# board_revA.net
KiCad netlist of a schematic drawn in EAGLE
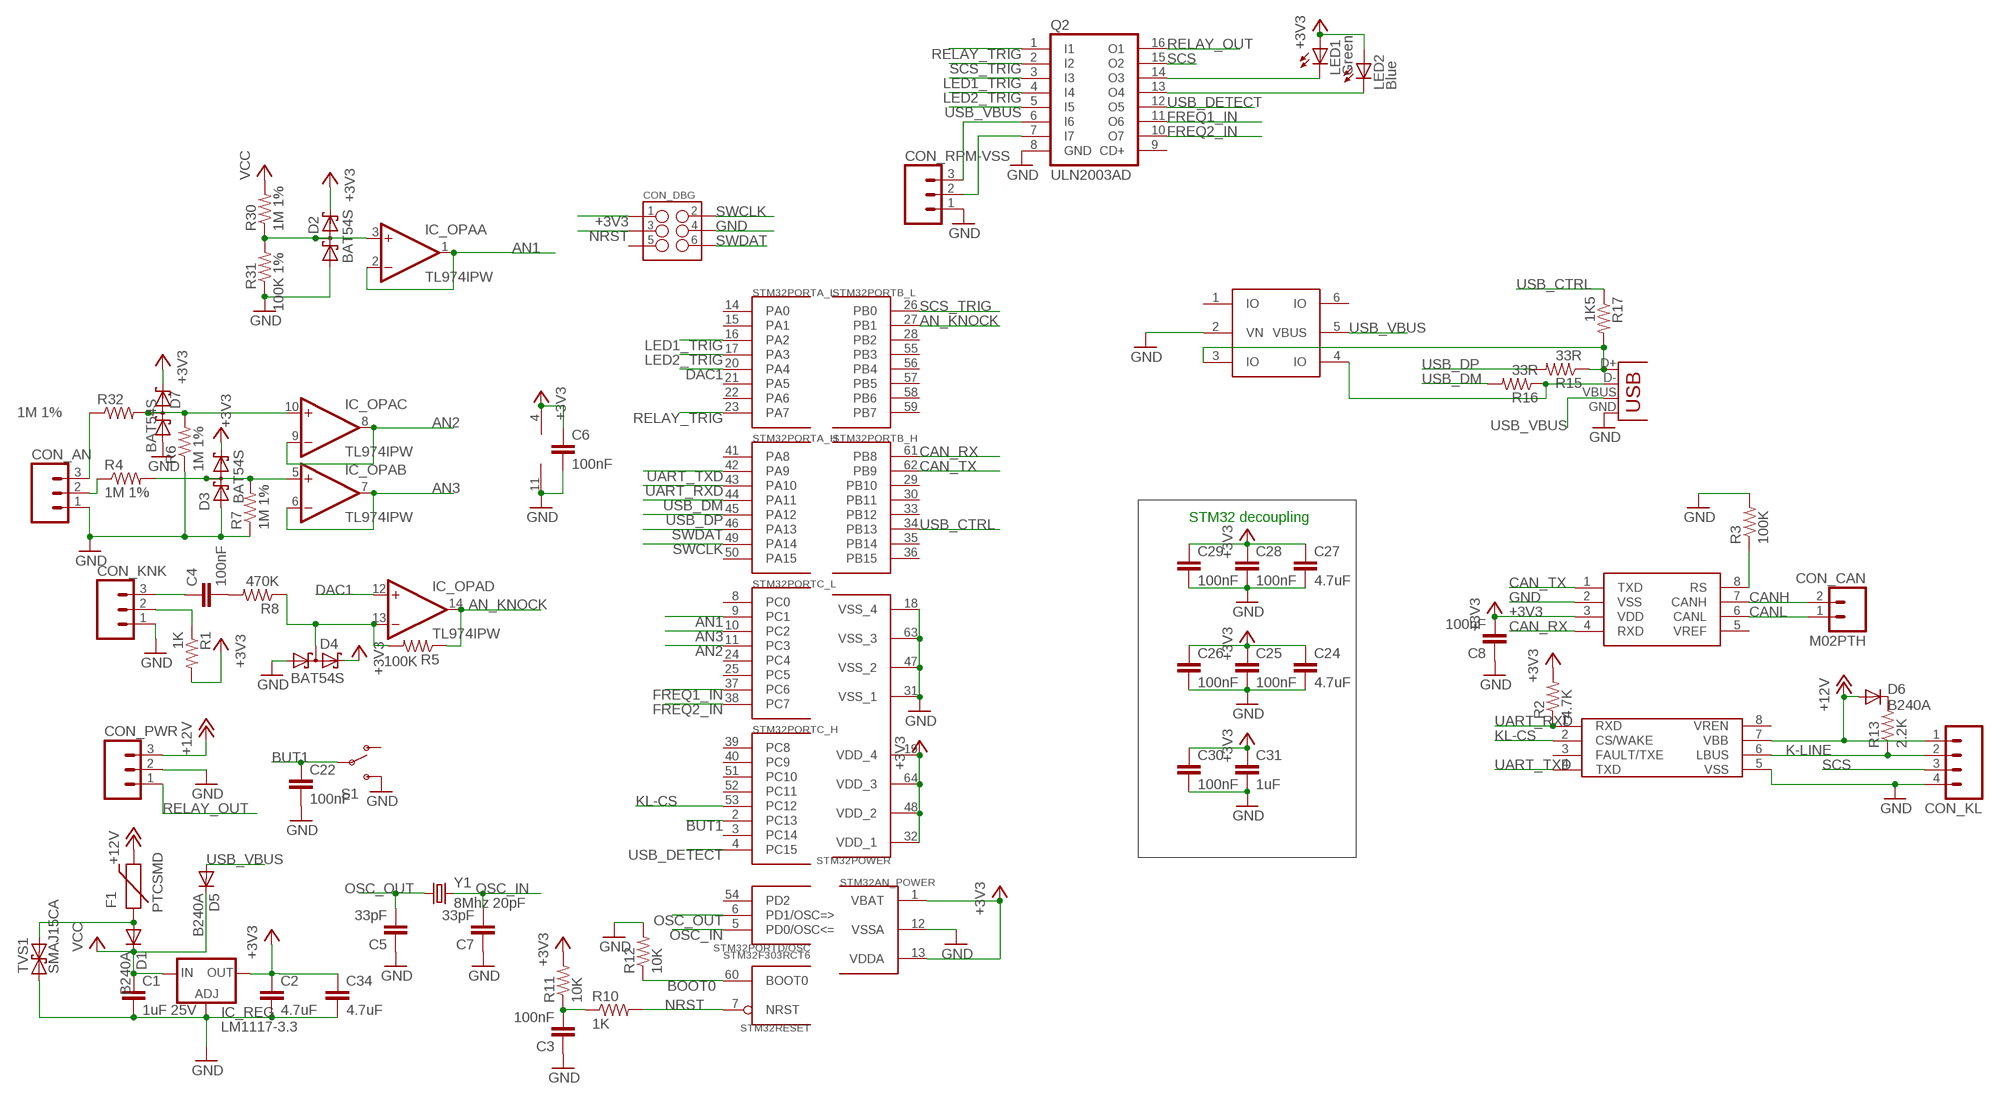
[diagram p0: schematic, sheet 1]

(export (version "E")
  (design (tool "Eeschema 10.0.6"))
  (components
    (comp (ref "C1")
      (value "1uF 25V")
      (footprint "eagle-import:0603-CAP")
      (libsource (lib "eagle-import") (part "SparkFun-Passives_CAP0603-CAP"))
    )
    (comp (ref "C2")
      (value "4.7uF")
      (footprint "eagle-import:0603-CAP")
      (libsource (lib "eagle-import") (part "SparkFun-Passives_CAP0603-CAP"))
    )
    (comp (ref "C3")
      (value "100nF")
      (footprint "eagle-import:0603-CAP")
      (libsource (lib "eagle-import") (part "CAP0603-CAP"))
    )
    (comp (ref "C4")
      (value "100nF")
      (footprint "eagle-import:0603-CAP")
      (libsource (lib "eagle-import") (part "CAP0603-CAP"))
    )
    (comp (ref "C5")
      (value "33pF")
      (footprint "eagle-import:0603-CAP")
      (libsource (lib "eagle-import") (part "CAP0603-CAP"))
    )
    (comp (ref "C6")
      (value "100nF")
      (footprint "eagle-import:0603-CAP")
      (libsource (lib "eagle-import") (part "CAP0603-CAP"))
    )
    (comp (ref "C7")
      (value "33pF")
      (footprint "eagle-import:0603-CAP")
      (libsource (lib "eagle-import") (part "CAP0603-CAP"))
    )
    (comp (ref "C8")
      (value "100nF")
      (footprint "eagle-import:0603-CAP")
      (libsource (lib "eagle-import") (part "CAP0603-CAP"))
    )
    (comp (ref "C22")
      (value "100nF")
      (footprint "eagle-import:0603-CAP")
      (libsource (lib "eagle-import") (part "CAP0603-CAP"))
    )
    (comp (ref "C24")
      (value "4.7uF")
      (footprint "eagle-import:0603-CAP")
      (libsource (lib "eagle-import") (part "SparkFun-Passives_CAP0603-CAP"))
    )
    (comp (ref "C25")
      (value "100nF")
      (footprint "eagle-import:0603-CAP")
      (libsource (lib "eagle-import") (part "CAP0603-CAP"))
    )
    (comp (ref "C26")
      (value "100nF")
      (footprint "eagle-import:0603-CAP")
      (libsource (lib "eagle-import") (part "CAP0603-CAP"))
    )
    (comp (ref "C27")
      (value "4.7uF")
      (footprint "eagle-import:0603-CAP")
      (libsource (lib "eagle-import") (part "SparkFun-Passives_CAP0603-CAP"))
    )
    (comp (ref "C28")
      (value "100nF")
      (footprint "eagle-import:0603-CAP")
      (libsource (lib "eagle-import") (part "CAP0603-CAP"))
    )
    (comp (ref "C29")
      (value "100nF")
      (footprint "eagle-import:0603-CAP")
      (libsource (lib "eagle-import") (part "CAP0603-CAP"))
    )
    (comp (ref "C30")
      (value "100nF")
      (footprint "eagle-import:0603-CAP")
      (libsource (lib "eagle-import") (part "CAP0603-CAP"))
    )
    (comp (ref "C31")
      (value "1uF")
      (footprint "eagle-import:0603-CAP")
      (libsource (lib "eagle-import") (part "CAP0603-CAP"))
    )
    (comp (ref "C34")
      (value "4.7uF")
      (footprint "eagle-import:0603-CAP")
      (libsource (lib "eagle-import") (part "SparkFun-Passives_CAP0603-CAP"))
    )
    (comp (ref "CON_AN")
      (value "M03PTH")
      (footprint "eagle-import:1X03")
      (libsource (lib "eagle-import") (part "M03PTH"))
    )
    (comp (ref "CON_CAN")
      (value "M02PTH")
      (footprint "eagle-import:1X02")
      (libsource (lib "eagle-import") (part "M02PTH"))
    )
    (comp (ref "CON_DBG")
      (value "M03X22X3_SILK_SM")
      (footprint "eagle-import:2X3")
      (libsource (lib "eagle-import") (part "M03X22X3_SILK_SM"))
    )
    (comp (ref "CON_KL")
      (value "M04PTH")
      (footprint "eagle-import:1X04")
      (libsource (lib "eagle-import") (part "M04PTH"))
    )
    (comp (ref "CON_KNK")
      (value "M03PTH")
      (footprint "eagle-import:1X03")
      (libsource (lib "eagle-import") (part "M03PTH"))
    )
    (comp (ref "CON_PWR")
      (value "M03PTH")
      (footprint "eagle-import:1X03")
      (libsource (lib "eagle-import") (part "M03PTH"))
    )
    (comp (ref "CON_RPM-VSS")
      (value "M03PTH")
      (footprint "eagle-import:1X03")
      (libsource (lib "eagle-import") (part "M03PTH"))
    )
    (comp (ref "CON_USB")
      (value "USBSMD")
      (footprint "eagle-import:USB-MINIB")
      (libsource (lib "eagle-import") (part "USBSMD"))
    )
    (comp (ref "D1")
      (value "B240A")
      (footprint "eagle-import:SMA-DIODE")
      (libsource (lib "eagle-import") (part "DIODESMA"))
    )
    (comp (ref "D2")
      (value "BAT54S")
      (footprint "eagle-import:SOT23")
      (libsource (lib "eagle-import") (part "BAT54S"))
    )
    (comp (ref "D3")
      (value "BAT54S")
      (footprint "eagle-import:SOT23")
      (libsource (lib "eagle-import") (part "BAT54S"))
    )
    (comp (ref "D4")
      (value "BAT54S")
      (footprint "eagle-import:SOT23")
      (libsource (lib "eagle-import") (part "BAT54S"))
    )
    (comp (ref "D5")
      (value "B240A")
      (footprint "eagle-import:SMA-DIODE")
      (libsource (lib "eagle-import") (part "DIODESMA"))
    )
    (comp (ref "D6")
      (value "B240A")
      (footprint "eagle-import:SMA-DIODE")
      (libsource (lib "eagle-import") (part "DIODESMA"))
    )
    (comp (ref "D7")
      (value "BAT54S")
      (footprint "eagle-import:SOT23")
      (libsource (lib "eagle-import") (part "BAT54S"))
    )
    (comp (ref "F1")
      (value "PTCSMD")
      (footprint "eagle-import:PTC-1206")
      (libsource (lib "eagle-import") (part "PTCSMD"))
    )
    (comp (ref "IC_CAN")
      (value "MAX3051")
      (footprint "eagle-import:SO08")
      (libsource (lib "eagle-import") (part "MCP2551"))
    )
    (comp (ref "IC_KLINE")
      (value "MCP2004")
      (footprint "eagle-import:SO08")
      (libsource (lib "eagle-import") (part "MCP2004"))
    )
    (comp (ref "IC_OPA")
      (value "TL974IPW")
      (footprint "eagle-import:TSSOP14")
      (libsource (lib "eagle-import") (part "LMV324?MZ"))
    )
    (comp (ref "IC_REG")
      (value "LM1117-3.3")
      (footprint "eagle-import:DPACK")
      (libsource (lib "eagle-import") (part "LD117A?DT33TR"))
    )
    (comp (ref "LED1")
      (value "Green")
      (footprint "eagle-import:LED3MM")
      (libsource (lib "eagle-import") (part "LED3MM"))
    )
    (comp (ref "LED2")
      (value "Blue")
      (footprint "eagle-import:LED3MM")
      (libsource (lib "eagle-import") (part "LED3MM"))
    )
    (comp (ref "Q2")
      (value "ULN2003AD")
      (footprint "eagle-import:SO16")
      (libsource (lib "eagle-import") (part "ULN2003AD"))
    )
    (comp (ref "R1")
      (value "1K")
      (footprint "eagle-import:0603-RES")
      (libsource (lib "eagle-import") (part "RESISTOR0603-RES"))
    )
    (comp (ref "R2")
      (value "4.7K")
      (footprint "eagle-import:0603-RES")
      (libsource (lib "eagle-import") (part "RESISTOR0603-RES"))
    )
    (comp (ref "R3")
      (value "100K")
      (footprint "eagle-import:0603-RES")
      (libsource (lib "eagle-import") (part "RESISTOR0603-RES"))
    )
    (comp (ref "R4")
      (value "1M 1%")
      (footprint "eagle-import:0603-RES")
      (libsource (lib "eagle-import") (part "RESISTOR0603-RES"))
    )
    (comp (ref "R5")
      (value "100K")
      (footprint "eagle-import:0603-RES")
      (libsource (lib "eagle-import") (part "RESISTOR0603-RES"))
    )
    (comp (ref "R6")
      (value "1M 1%")
      (footprint "eagle-import:0603-RES")
      (libsource (lib "eagle-import") (part "RESISTOR0603-RES"))
    )
    (comp (ref "R7")
      (value "1M 1%")
      (footprint "eagle-import:0603-RES")
      (libsource (lib "eagle-import") (part "RESISTOR0603-RES"))
    )
    (comp (ref "R8")
      (value "470K")
      (footprint "eagle-import:0603-RES")
      (libsource (lib "eagle-import") (part "RESISTOR0603-RES"))
    )
    (comp (ref "R10")
      (value "1K")
      (footprint "eagle-import:0603-RES")
      (libsource (lib "eagle-import") (part "RESISTOR0603-RES"))
    )
    (comp (ref "R11")
      (value "10K")
      (footprint "eagle-import:0603-RES")
      (libsource (lib "eagle-import") (part "RESISTOR0603-RES"))
    )
    (comp (ref "R12")
      (value "10K")
      (footprint "eagle-import:0603-RES")
      (libsource (lib "eagle-import") (part "RESISTOR0603-RES"))
    )
    (comp (ref "R13")
      (value "2.2K")
      (footprint "eagle-import:0603-RES")
      (libsource (lib "eagle-import") (part "RESISTOR0603-RES"))
    )
    (comp (ref "R15")
      (value "33R")
      (footprint "eagle-import:0603-RES")
      (libsource (lib "eagle-import") (part "RESISTOR0603-RES"))
    )
    (comp (ref "R16")
      (value "33R")
      (footprint "eagle-import:0603-RES")
      (libsource (lib "eagle-import") (part "RESISTOR0603-RES"))
    )
    (comp (ref "R17")
      (value "1K5")
      (footprint "eagle-import:0603-RES")
      (libsource (lib "eagle-import") (part "RESISTOR0603-RES"))
    )
    (comp (ref "R30")
      (value "1M 1%")
      (footprint "eagle-import:0603-RES")
      (libsource (lib "eagle-import") (part "RESISTOR0603-RES"))
    )
    (comp (ref "R31")
      (value "100K 1%")
      (footprint "eagle-import:0603-RES")
      (libsource (lib "eagle-import") (part "RESISTOR0603-RES"))
    )
    (comp (ref "R32")
      (value "1M 1%")
      (footprint "eagle-import:0603-RES")
      (libsource (lib "eagle-import") (part "RESISTOR0603-RES"))
    )
    (comp (ref "S1")
      (value "SWITCH-SPDTPTH")
      (footprint "eagle-import:SWITCH-SPDT")
      (libsource (lib "eagle-import") (part "SWITCH-SPDTPTH"))
    )
    (comp (ref "STM32")
      (value "STM32F303RCT6")
      (footprint "eagle-import:TQFP64")
      (libsource (lib "eagle-import") (part "STM32F10XRXT6"))
    )
    (comp (ref "TVS1")
      (value "SMAJ15CA")
      (footprint "eagle-import:SMA-DIODE")
      (libsource (lib "eagle-import") (part "TVS"))
    )
    (comp (ref "TVS2")
      (value "NUP4201MR6")
      (footprint "eagle-import:SOT23-6")
      (libsource (lib "eagle-import") (part "NUP4201MR6"))
    )
    (comp (ref "Y1")
      (value "8Mhz 20pF")
      (footprint "eagle-import:HC49US")
      (libsource (lib "eagle-import") (part "CRYSTALHC49US"))
    )
  )
  (nets
    (net (code "1") (name "+3V3") (class "Default")
      (node (ref "C2") (pin "1") (pinfunction "1_1") (pintype "passive"))
      (node (ref "C24") (pin "1") (pinfunction "1_1") (pintype "passive"))
      (node (ref "C25") (pin "1") (pinfunction "1_1") (pintype "passive"))
      (node (ref "C26") (pin "1") (pinfunction "1_1") (pintype "passive"))
      (node (ref "C27") (pin "1") (pinfunction "1_1") (pintype "passive"))
      (node (ref "C28") (pin "1") (pinfunction "1_1") (pintype "passive"))
      (node (ref "C29") (pin "1") (pinfunction "1_1") (pintype "passive"))
      (node (ref "C30") (pin "1") (pinfunction "1_1") (pintype "passive"))
      (node (ref "C31") (pin "1") (pinfunction "1_1") (pintype "passive"))
      (node (ref "C34") (pin "1") (pinfunction "1_1") (pintype "passive"))
      (node (ref "C6") (pin "1") (pinfunction "1_1") (pintype "passive"))
      (node (ref "C8") (pin "2") (pinfunction "2_2") (pintype "passive"))
      (node (ref "CON_DBG") (pin "1") (pinfunction "1_1") (pintype "bidirectional"))
      (node (ref "D2") (pin "2") (pinfunction "C2_2") (pintype "passive"))
      (node (ref "D3") (pin "2") (pinfunction "C2_2") (pintype "passive"))
      (node (ref "D4") (pin "2") (pinfunction "C2_2") (pintype "passive"))
      (node (ref "D7") (pin "2") (pinfunction "C2_2") (pintype "passive"))
      (node (ref "IC_CAN") (pin "3") (pinfunction "VDD_3") (pintype "bidirectional"))
      (node (ref "IC_OPA") (pin "4") (pinfunction "V+_4") (pintype "power_in"))
      (node (ref "IC_REG") (pin "4") (pinfunction "OUT_4") (pintype "passive"))
      (node (ref "LED1") (pin "A") (pinfunction "A_A") (pintype "passive"))
      (node (ref "LED2") (pin "A") (pinfunction "A_A") (pintype "passive"))
      (node (ref "R1") (pin "2") (pinfunction "2_2") (pintype "passive"))
      (node (ref "R11") (pin "2") (pinfunction "2_2") (pintype "passive"))
      (node (ref "R2") (pin "2") (pinfunction "2_2") (pintype "passive"))
      (node (ref "STM32") (pin "1") (pinfunction "VBAT_1") (pintype "power_in"))
      (node (ref "STM32") (pin "13") (pinfunction "VDDA_13") (pintype "power_in"))
      (node (ref "STM32") (pin "19") (pinfunction "VDD_4_19") (pintype "power_in"))
      (node (ref "STM32") (pin "32") (pinfunction "VDD_1_32") (pintype "power_in"))
      (node (ref "STM32") (pin "48") (pinfunction "VDD_2_48") (pintype "power_in"))
      (node (ref "STM32") (pin "64") (pinfunction "VDD_3_64") (pintype "power_in"))
    )
    (net (code "2") (name "+12V") (class "Default")
      (node (ref "CON_KL") (pin "1") (pinfunction "1_1") (pintype "passive"))
      (node (ref "CON_PWR") (pin "3") (pinfunction "3_3") (pintype "passive"))
      (node (ref "D6") (pin "A") (pinfunction "A_A") (pintype "passive"))
      (node (ref "F1") (pin "2") (pinfunction "2_2") (pintype "bidirectional"))
      (node (ref "IC_KLINE") (pin "7") (pinfunction "VBB_7") (pintype "bidirectional"))
    )
    (net (code "3") (name "/AN1") (class "Default")
      (node (ref "IC_OPA") (pin "1") (pinfunction "OUT_1") (pintype "output"))
      (node (ref "IC_OPA") (pin "2") (pinfunction "-IN_2") (pintype "input"))
      (node (ref "STM32") (pin "9") (pinfunction "PC1_9") (pintype "bidirectional"))
    )
    (net (code "4") (name "/AN2") (class "Default")
      (node (ref "IC_OPA") (pin "8") (pinfunction "OUT_8") (pintype "output"))
      (node (ref "IC_OPA") (pin "9") (pinfunction "-IN_9") (pintype "input"))
      (node (ref "STM32") (pin "11") (pinfunction "PC3_11") (pintype "bidirectional"))
    )
    (net (code "5") (name "/AN3") (class "Default")
      (node (ref "IC_OPA") (pin "6") (pinfunction "-IN_6") (pintype "input"))
      (node (ref "IC_OPA") (pin "7") (pinfunction "OUT_7") (pintype "output"))
      (node (ref "STM32") (pin "10") (pinfunction "PC2_10") (pintype "bidirectional"))
    )
    (net (code "6") (name "/AN_KNOCK") (class "Default")
      (node (ref "IC_OPA") (pin "14") (pinfunction "OUT_14") (pintype "output"))
      (node (ref "R5") (pin "1") (pinfunction "1_1") (pintype "passive"))
      (node (ref "STM32") (pin "27") (pinfunction "PB1_27") (pintype "bidirectional"))
    )
    (net (code "7") (name "/BOOT0") (class "Default")
      (node (ref "R12") (pin "1") (pinfunction "1_1") (pintype "passive"))
      (node (ref "STM32") (pin "60") (pinfunction "BOOT0_60") (pintype "input"))
    )
    (net (code "8") (name "/BUT1") (class "Default")
      (node (ref "C22") (pin "1") (pinfunction "1_1") (pintype "passive"))
      (node (ref "S1") (pin "2") (pinfunction "P_2") (pintype "passive"))
      (node (ref "STM32") (pin "2") (pinfunction "PC13_2") (pintype "bidirectional"))
    )
    (net (code "9") (name "/CANH") (class "Default")
      (node (ref "CON_CAN") (pin "2") (pinfunction "2_2") (pintype "passive"))
      (node (ref "IC_CAN") (pin "7") (pinfunction "CANH_7") (pintype "bidirectional"))
    )
    (net (code "10") (name "/CANL") (class "Default")
      (node (ref "CON_CAN") (pin "1") (pinfunction "1_1") (pintype "passive"))
      (node (ref "IC_CAN") (pin "6") (pinfunction "CANL_6") (pintype "bidirectional"))
    )
    (net (code "11") (name "/CAN_RX") (class "Default")
      (node (ref "IC_CAN") (pin "4") (pinfunction "RXD_4") (pintype "bidirectional"))
      (node (ref "STM32") (pin "61") (pinfunction "PB8_61") (pintype "bidirectional"))
    )
    (net (code "12") (name "/CAN_TX") (class "Default")
      (node (ref "IC_CAN") (pin "1") (pinfunction "TXD_1") (pintype "bidirectional"))
      (node (ref "STM32") (pin "62") (pinfunction "PB9_62") (pintype "bidirectional"))
    )
    (net (code "13") (name "/DAC1") (class "Default")
      (node (ref "IC_OPA") (pin "12") (pinfunction "+IN_12") (pintype "input"))
      (node (ref "STM32") (pin "20") (pinfunction "PA4_20") (pintype "bidirectional"))
    )
    (net (code "14") (name "/FREQ1_IN") (class "Default")
      (node (ref "Q2") (pin "11") (pinfunction "O6_11") (pintype "open_collector"))
      (node (ref "STM32") (pin "37") (pinfunction "PC6_37") (pintype "bidirectional"))
    )
    (net (code "15") (name "/FREQ2_IN") (class "Default")
      (node (ref "Q2") (pin "10") (pinfunction "O7_10") (pintype "open_collector"))
      (node (ref "STM32") (pin "38") (pinfunction "PC7_38") (pintype "bidirectional"))
    )
    (net (code "16") (name "/K-LINE") (class "Default")
      (node (ref "CON_KL") (pin "2") (pinfunction "2_2") (pintype "passive"))
      (node (ref "IC_KLINE") (pin "6") (pinfunction "LBUS_6") (pintype "bidirectional"))
      (node (ref "R13") (pin "1") (pinfunction "1_1") (pintype "passive"))
    )
    (net (code "17") (name "/KL-CS") (class "Default")
      (node (ref "IC_KLINE") (pin "2") (pinfunction "CS/WAKE_2") (pintype "bidirectional"))
      (node (ref "STM32") (pin "53") (pinfunction "PC12_53") (pintype "bidirectional"))
    )
    (net (code "18") (name "/LED1_TRIG") (class "Default")
      (node (ref "Q2") (pin "3") (pinfunction "I3_3") (pintype "input"))
      (node (ref "STM32") (pin "16") (pinfunction "PA2_16") (pintype "bidirectional"))
    )
    (net (code "19") (name "/LED2_TRIG") (class "Default")
      (node (ref "Q2") (pin "4") (pinfunction "I4_4") (pintype "input"))
      (node (ref "STM32") (pin "17") (pinfunction "PA3_17") (pintype "bidirectional"))
    )
    (net (code "20") (name "/NRST") (class "Default")
      (node (ref "CON_DBG") (pin "3") (pinfunction "3_3") (pintype "bidirectional"))
      (node (ref "R10") (pin "2") (pinfunction "2_2") (pintype "passive"))
      (node (ref "STM32") (pin "7") (pinfunction "NRST_7") (pintype "input"))
    )
    (net (code "21") (name "/OSC_IN") (class "Default")
      (node (ref "C7") (pin "2") (pinfunction "2_2") (pintype "passive"))
      (node (ref "STM32") (pin "5") (pinfunction "PD0/OSC<=_5") (pintype "bidirectional"))
      (node (ref "Y1") (pin "2") (pinfunction "2_2") (pintype "passive"))
    )
    (net (code "22") (name "/OSC_OUT") (class "Default")
      (node (ref "C5") (pin "2") (pinfunction "2_2") (pintype "passive"))
      (node (ref "STM32") (pin "6") (pinfunction "PD1/OSC=>_6") (pintype "bidirectional"))
      (node (ref "Y1") (pin "1") (pinfunction "1_1") (pintype "passive"))
    )
    (net (code "23") (name "/RELAY_OUT") (class "Default")
      (node (ref "CON_PWR") (pin "1") (pinfunction "1_1") (pintype "passive"))
      (node (ref "Q2") (pin "16") (pinfunction "O1_16") (pintype "open_collector"))
    )
    (net (code "24") (name "/RELAY_TRIG") (class "Default")
      (node (ref "Q2") (pin "1") (pinfunction "I1_1") (pintype "input"))
      (node (ref "STM32") (pin "23") (pinfunction "PA7_23") (pintype "bidirectional"))
    )
    (net (code "25") (name "/SCS") (class "Default")
      (node (ref "CON_KL") (pin "3") (pinfunction "3_3") (pintype "passive"))
      (node (ref "Q2") (pin "15") (pinfunction "O2_15") (pintype "open_collector"))
    )
    (net (code "26") (name "/SCS_TRIG") (class "Default")
      (node (ref "Q2") (pin "2") (pinfunction "I2_2") (pintype "input"))
      (node (ref "STM32") (pin "26") (pinfunction "PB0_26") (pintype "bidirectional"))
    )
    (net (code "27") (name "/SWCLK") (class "Default")
      (node (ref "CON_DBG") (pin "2") (pinfunction "2_2") (pintype "bidirectional"))
      (node (ref "STM32") (pin "49") (pinfunction "PA14_49") (pintype "bidirectional"))
    )
    (net (code "28") (name "/SWDAT") (class "Default")
      (node (ref "CON_DBG") (pin "6") (pinfunction "6_6") (pintype "bidirectional"))
      (node (ref "STM32") (pin "46") (pinfunction "PA13_46") (pintype "bidirectional"))
    )
    (net (code "29") (name "/UART_RXD") (class "Default")
      (node (ref "IC_KLINE") (pin "1") (pinfunction "RXD_1") (pintype "bidirectional"))
      (node (ref "R2") (pin "1") (pinfunction "1_1") (pintype "passive"))
      (node (ref "STM32") (pin "43") (pinfunction "PA10_43") (pintype "bidirectional"))
    )
    (net (code "30") (name "/UART_TXD") (class "Default")
      (node (ref "IC_KLINE") (pin "4") (pinfunction "TXD_4") (pintype "bidirectional"))
      (node (ref "STM32") (pin "42") (pinfunction "PA9_42") (pintype "bidirectional"))
    )
    (net (code "31") (name "/USB_CTRL") (class "Default")
      (node (ref "R17") (pin "1") (pinfunction "1_1") (pintype "passive"))
      (node (ref "STM32") (pin "34") (pinfunction "PB13_34") (pintype "bidirectional"))
    )
    (net (code "32") (name "/USB_DETECT") (class "Default")
      (node (ref "Q2") (pin "12") (pinfunction "O5_12") (pintype "open_collector"))
      (node (ref "STM32") (pin "4") (pinfunction "PC15_4") (pintype "bidirectional"))
    )
    (net (code "33") (name "/USB_DM") (class "Default")
      (node (ref "R16") (pin "2") (pinfunction "2_2") (pintype "passive"))
      (node (ref "STM32") (pin "44") (pinfunction "PA11_44") (pintype "bidirectional"))
    )
    (net (code "34") (name "/USB_DP") (class "Default")
      (node (ref "R15") (pin "2") (pinfunction "2_2") (pintype "passive"))
      (node (ref "STM32") (pin "45") (pinfunction "PA12_45") (pintype "bidirectional"))
    )
    (net (code "35") (name "/USB_VBUS") (class "Default")
      (node (ref "CON_USB") (pin "VBUS") (pinfunction "VBUS_VBUS") (pintype "bidirectional"))
      (node (ref "D5") (pin "A") (pinfunction "A_A") (pintype "passive"))
      (node (ref "Q2") (pin "5") (pinfunction "I5_5") (pintype "input"))
      (node (ref "TVS2") (pin "5") (pinfunction "VBUS_5") (pintype "power_in"))
    )
    (net (code "36") (name "GND") (class "Default")
      (node (ref "C1") (pin "2") (pinfunction "2_2") (pintype "passive"))
      (node (ref "C2") (pin "2") (pinfunction "2_2") (pintype "passive"))
      (node (ref "C22") (pin "2") (pinfunction "2_2") (pintype "passive"))
      (node (ref "C24") (pin "2") (pinfunction "2_2") (pintype "passive"))
      (node (ref "C25") (pin "2") (pinfunction "2_2") (pintype "passive"))
      (node (ref "C26") (pin "2") (pinfunction "2_2") (pintype "passive"))
      (node (ref "C27") (pin "2") (pinfunction "2_2") (pintype "passive"))
      (node (ref "C28") (pin "2") (pinfunction "2_2") (pintype "passive"))
      (node (ref "C29") (pin "2") (pinfunction "2_2") (pintype "passive"))
      (node (ref "C3") (pin "1") (pinfunction "1_1") (pintype "passive"))
      (node (ref "C30") (pin "2") (pinfunction "2_2") (pintype "passive"))
      (node (ref "C31") (pin "2") (pinfunction "2_2") (pintype "passive"))
      (node (ref "C34") (pin "2") (pinfunction "2_2") (pintype "passive"))
      (node (ref "C5") (pin "1") (pinfunction "1_1") (pintype "passive"))
      (node (ref "C6") (pin "2") (pinfunction "2_2") (pintype "passive"))
      (node (ref "C7") (pin "1") (pinfunction "1_1") (pintype "passive"))
      (node (ref "C8") (pin "1") (pinfunction "1_1") (pintype "passive"))
      (node (ref "CON_AN") (pin "1") (pinfunction "1_1") (pintype "passive"))
      (node (ref "CON_DBG") (pin "4") (pinfunction "4_4") (pintype "bidirectional"))
      (node (ref "CON_KL") (pin "4") (pinfunction "4_4") (pintype "passive"))
      (node (ref "CON_KNK") (pin "1") (pinfunction "1_1") (pintype "passive"))
      (node (ref "CON_PWR") (pin "2") (pinfunction "2_2") (pintype "passive"))
      (node (ref "CON_RPM-VSS") (pin "1") (pinfunction "1_1") (pintype "passive"))
      (node (ref "CON_USB") (pin "GND") (pinfunction "GND_GND") (pintype "bidirectional"))
      (node (ref "D2") (pin "1") (pinfunction "A1_1") (pintype "passive"))
      (node (ref "D3") (pin "1") (pinfunction "A1_1") (pintype "passive"))
      (node (ref "D4") (pin "1") (pinfunction "A1_1") (pintype "passive"))
      (node (ref "D7") (pin "1") (pinfunction "A1_1") (pintype "passive"))
      (node (ref "IC_CAN") (pin "2") (pinfunction "VSS_2") (pintype "bidirectional"))
      (node (ref "IC_KLINE") (pin "5") (pinfunction "VSS_5") (pintype "bidirectional"))
      (node (ref "IC_OPA") (pin "11") (pinfunction "V-_11") (pintype "power_in"))
      (node (ref "IC_REG") (pin "1") (pinfunction "ADJ_1") (pintype "input"))
      (node (ref "Q2") (pin "8") (pinfunction "GND_8") (pintype "power_in"))
      (node (ref "R12") (pin "2") (pinfunction "2_2") (pintype "passive"))
      (node (ref "R3") (pin "2") (pinfunction "2_2") (pintype "passive"))
      (node (ref "R31") (pin "1") (pinfunction "1_1") (pintype "passive"))
      (node (ref "R6") (pin "1") (pinfunction "1_1") (pintype "passive"))
      (node (ref "R7") (pin "1") (pinfunction "1_1") (pintype "passive"))
      (node (ref "S1") (pin "3") (pinfunction "S_3") (pintype "passive"))
      (node (ref "STM32") (pin "12") (pinfunction "VSSA_12") (pintype "power_in"))
      (node (ref "STM32") (pin "18") (pinfunction "VSS_4_18") (pintype "power_in"))
      (node (ref "STM32") (pin "31") (pinfunction "VSS_1_31") (pintype "power_in"))
      (node (ref "STM32") (pin "47") (pinfunction "VSS_2_47") (pintype "power_in"))
      (node (ref "STM32") (pin "63") (pinfunction "VSS_3_63") (pintype "power_in"))
      (node (ref "TVS1") (pin "A") (pinfunction "1_A") (pintype "passive"))
      (node (ref "TVS2") (pin "2") (pinfunction "VN_2") (pintype "power_in"))
    )
    (net (code "37") (name "Net-(C3-Pad2)") (class "Default")
      (node (ref "C3") (pin "2") (pinfunction "2_2") (pintype "passive"))
      (node (ref "R10") (pin "1") (pinfunction "1_1") (pintype "passive"))
      (node (ref "R11") (pin "1") (pinfunction "1_1") (pintype "passive"))
    )
    (net (code "38") (name "Net-(C4-Pad1)") (class "Default")
      (node (ref "C4") (pin "1") (pinfunction "1_1") (pintype "passive"))
      (node (ref "CON_KNK") (pin "3") (pinfunction "3_3") (pintype "passive"))
    )
    (net (code "39") (name "Net-(C4-Pad2)") (class "Default")
      (node (ref "C4") (pin "2") (pinfunction "2_2") (pintype "passive"))
      (node (ref "R8") (pin "2") (pinfunction "2_2") (pintype "passive"))
    )
    (net (code "40") (name "Net-(CON_AN-Pad2)") (class "Default")
      (node (ref "CON_AN") (pin "2") (pinfunction "2_2") (pintype "passive"))
      (node (ref "R4") (pin "1") (pinfunction "1_1") (pintype "passive"))
    )
    (net (code "41") (name "Net-(CON_AN-Pad3)") (class "Default")
      (node (ref "CON_AN") (pin "3") (pinfunction "3_3") (pintype "passive"))
      (node (ref "R32") (pin "1") (pinfunction "1_1") (pintype "passive"))
    )
    (net (code "42") (name "Net-(CON_KNK-Pad2)") (class "Default")
      (node (ref "CON_KNK") (pin "2") (pinfunction "2_2") (pintype "passive"))
      (node (ref "R1") (pin "1") (pinfunction "1_1") (pintype "passive"))
    )
    (net (code "43") (name "Net-(CON_USB-PadD+)") (class "Default")
      (node (ref "CON_USB") (pin "D+") (pinfunction "D+_D+") (pintype "bidirectional"))
      (node (ref "R15") (pin "1") (pinfunction "1_1") (pintype "passive"))
      (node (ref "R17") (pin "2") (pinfunction "2_2") (pintype "passive"))
      (node (ref "TVS2") (pin "3") (pinfunction "IO_3") (pintype "bidirectional"))
    )
    (net (code "44") (name "Net-(CON_USB-PadD-)") (class "Default")
      (node (ref "CON_USB") (pin "D-") (pinfunction "D-_D-") (pintype "bidirectional"))
      (node (ref "R16") (pin "1") (pinfunction "1_1") (pintype "passive"))
      (node (ref "TVS2") (pin "4") (pinfunction "IO_4") (pintype "bidirectional"))
    )
    (net (code "45") (name "Net-(D2-C1A2)") (class "Default")
      (node (ref "D2") (pin "3") (pinfunction "C1A2_3") (pintype "passive"))
      (node (ref "IC_OPA") (pin "3") (pinfunction "+IN_3") (pintype "input"))
      (node (ref "R30") (pin "1") (pinfunction "1_1") (pintype "passive"))
      (node (ref "R31") (pin "2") (pinfunction "2_2") (pintype "passive"))
    )
    (net (code "46") (name "Net-(D3-C1A2)") (class "Default")
      (node (ref "D3") (pin "3") (pinfunction "C1A2_3") (pintype "passive"))
      (node (ref "IC_OPA") (pin "5") (pinfunction "+IN_5") (pintype "input"))
      (node (ref "R4") (pin "2") (pinfunction "2_2") (pintype "passive"))
      (node (ref "R7") (pin "2") (pinfunction "2_2") (pintype "passive"))
    )
    (net (code "47") (name "Net-(D4-C1A2)") (class "Default")
      (node (ref "D4") (pin "3") (pinfunction "C1A2_3") (pintype "passive"))
      (node (ref "IC_OPA") (pin "13") (pinfunction "-IN_13") (pintype "input"))
      (node (ref "R5") (pin "2") (pinfunction "2_2") (pintype "passive"))
      (node (ref "R8") (pin "1") (pinfunction "1_1") (pintype "passive"))
    )
    (net (code "48") (name "Net-(D6-PadC)") (class "Default")
      (node (ref "D6") (pin "C") (pinfunction "C_C") (pintype "passive"))
      (node (ref "R13") (pin "2") (pinfunction "2_2") (pintype "passive"))
    )
    (net (code "49") (name "Net-(D7-C1A2)") (class "Default")
      (node (ref "D7") (pin "3") (pinfunction "C1A2_3") (pintype "passive"))
      (node (ref "IC_OPA") (pin "10") (pinfunction "+IN_10") (pintype "input"))
      (node (ref "R32") (pin "2") (pinfunction "2_2") (pintype "passive"))
      (node (ref "R6") (pin "2") (pinfunction "2_2") (pintype "passive"))
    )
    (net (code "50") (name "Net-(IC_CAN-RS)") (class "Default")
      (node (ref "IC_CAN") (pin "8") (pinfunction "RS_8") (pintype "bidirectional"))
      (node (ref "R3") (pin "1") (pinfunction "1_1") (pintype "passive"))
    )
    (net (code "51") (name "Net-(LED1-C)") (class "Default")
      (node (ref "LED1") (pin "K") (pinfunction "C_K") (pintype "passive"))
      (node (ref "Q2") (pin "14") (pinfunction "O3_14") (pintype "open_collector"))
    )
    (net (code "52") (name "Net-(LED2-C)") (class "Default")
      (node (ref "LED2") (pin "K") (pinfunction "C_K") (pintype "passive"))
      (node (ref "Q2") (pin "13") (pinfunction "O4_13") (pintype "open_collector"))
    )
    (net (code "53") (name "Net-(Q2-I6)") (class "Default")
      (node (ref "CON_RPM-VSS") (pin "3") (pinfunction "3_3") (pintype "passive"))
      (node (ref "Q2") (pin "6") (pinfunction "I6_6") (pintype "input"))
    )
    (net (code "54") (name "Net-(Q2-I7)") (class "Default")
      (node (ref "CON_RPM-VSS") (pin "2") (pinfunction "2_2") (pintype "passive"))
      (node (ref "Q2") (pin "7") (pinfunction "I7_7") (pintype "input"))
    )
    (net (code "55") (name "Net-(TVS1-2)") (class "Default")
      (node (ref "D1") (pin "A") (pinfunction "A_A") (pintype "passive"))
      (node (ref "F1") (pin "1") (pinfunction "1_1") (pintype "bidirectional"))
      (node (ref "TVS1") (pin "C") (pinfunction "2_C") (pintype "passive"))
    )
    (net (code "56") (name "VCC") (class "Default")
      (node (ref "C1") (pin "1") (pinfunction "1_1") (pintype "passive"))
      (node (ref "D1") (pin "C") (pinfunction "C_C") (pintype "passive"))
      (node (ref "D5") (pin "C") (pinfunction "C_C") (pintype "passive"))
      (node (ref "IC_REG") (pin "3") (pinfunction "IN_3") (pintype "input"))
      (node (ref "R30") (pin "2") (pinfunction "2_2") (pintype "passive"))
    )
    (net (code "57") (name "unconnected-(CON_DBG-Pad5)") (class "Default")
      (node (ref "CON_DBG") (pin "5") (pinfunction "5_5") (pintype "bidirectional"))
    )
    (net (code "58") (name "unconnected-(IC_CAN-VREF-Pad5)") (class "Default")
      (node (ref "IC_CAN") (pin "5") (pinfunction "VREF_5") (pintype "bidirectional"))
    )
    (net (code "59") (name "unconnected-(IC_KLINE-FAULT{slash}TXE-Pad3)") (class "Default")
      (node (ref "IC_KLINE") (pin "3") (pinfunction "FAULT/TXE_3") (pintype "bidirectional"))
    )
    (net (code "60") (name "unconnected-(IC_KLINE-VREN-Pad8)") (class "Default")
      (node (ref "IC_KLINE") (pin "8") (pinfunction "VREN_8") (pintype "bidirectional"))
    )
    (net (code "61") (name "unconnected-(Q2-CD+-Pad9)") (class "Default")
      (node (ref "Q2") (pin "9") (pinfunction "CD+_9") (pintype "passive"))
    )
    (net (code "62") (name "unconnected-(S1-O-Pad1)") (class "Default")
      (node (ref "S1") (pin "1") (pinfunction "O_1") (pintype "passive"))
    )
    (net (code "63") (name "unconnected-(STM32B-PA8-Pad41)") (class "Default")
      (node (ref "STM32") (pin "41") (pinfunction "PA8_41") (pintype "bidirectional"))
    )
    (net (code "64") (name "unconnected-(STM32B-PA15-Pad50)") (class "Default")
      (node (ref "STM32") (pin "50") (pinfunction "PA15_50") (pintype "bidirectional"))
    )
    (net (code "65") (name "unconnected-(STM32C-PA0-Pad14)") (class "Default")
      (node (ref "STM32") (pin "14") (pinfunction "PA0_14") (pintype "bidirectional"))
    )
    (net (code "66") (name "unconnected-(STM32C-PA1-Pad15)") (class "Default")
      (node (ref "STM32") (pin "15") (pinfunction "PA1_15") (pintype "bidirectional"))
    )
    (net (code "67") (name "unconnected-(STM32C-PA5-Pad21)") (class "Default")
      (node (ref "STM32") (pin "21") (pinfunction "PA5_21") (pintype "bidirectional"))
    )
    (net (code "68") (name "unconnected-(STM32C-PA6-Pad22)") (class "Default")
      (node (ref "STM32") (pin "22") (pinfunction "PA6_22") (pintype "bidirectional"))
    )
    (net (code "69") (name "unconnected-(STM32D-PB10-Pad29)") (class "Default")
      (node (ref "STM32") (pin "29") (pinfunction "PB10_29") (pintype "bidirectional"))
    )
    (net (code "70") (name "unconnected-(STM32D-PB11-Pad30)") (class "Default")
      (node (ref "STM32") (pin "30") (pinfunction "PB11_30") (pintype "bidirectional"))
    )
    (net (code "71") (name "unconnected-(STM32D-PB12-Pad33)") (class "Default")
      (node (ref "STM32") (pin "33") (pinfunction "PB12_33") (pintype "bidirectional"))
    )
    (net (code "72") (name "unconnected-(STM32D-PB14-Pad35)") (class "Default")
      (node (ref "STM32") (pin "35") (pinfunction "PB14_35") (pintype "bidirectional"))
    )
    (net (code "73") (name "unconnected-(STM32D-PB15-Pad36)") (class "Default")
      (node (ref "STM32") (pin "36") (pinfunction "PB15_36") (pintype "bidirectional"))
    )
    (net (code "74") (name "unconnected-(STM32E-PB2-Pad28)") (class "Default")
      (node (ref "STM32") (pin "28") (pinfunction "PB2_28") (pintype "bidirectional"))
    )
    (net (code "75") (name "unconnected-(STM32E-PB3-Pad55)") (class "Default")
      (node (ref "STM32") (pin "55") (pinfunction "PB3_55") (pintype "bidirectional"))
    )
    (net (code "76") (name "unconnected-(STM32E-PB4-Pad56)") (class "Default")
      (node (ref "STM32") (pin "56") (pinfunction "PB4_56") (pintype "bidirectional"))
    )
    (net (code "77") (name "unconnected-(STM32E-PB5-Pad57)") (class "Default")
      (node (ref "STM32") (pin "57") (pinfunction "PB5_57") (pintype "bidirectional"))
    )
    (net (code "78") (name "unconnected-(STM32E-PB6-Pad58)") (class "Default")
      (node (ref "STM32") (pin "58") (pinfunction "PB6_58") (pintype "bidirectional"))
    )
    (net (code "79") (name "unconnected-(STM32E-PB7-Pad59)") (class "Default")
      (node (ref "STM32") (pin "59") (pinfunction "PB7_59") (pintype "bidirectional"))
    )
    (net (code "80") (name "unconnected-(STM32F-PC8-Pad39)") (class "Default")
      (node (ref "STM32") (pin "39") (pinfunction "PC8_39") (pintype "bidirectional"))
    )
    (net (code "81") (name "unconnected-(STM32F-PC9-Pad40)") (class "Default")
      (node (ref "STM32") (pin "40") (pinfunction "PC9_40") (pintype "bidirectional"))
    )
    (net (code "82") (name "unconnected-(STM32F-PC10-Pad51)") (class "Default")
      (node (ref "STM32") (pin "51") (pinfunction "PC10_51") (pintype "bidirectional"))
    )
    (net (code "83") (name "unconnected-(STM32F-PC11-Pad52)") (class "Default")
      (node (ref "STM32") (pin "52") (pinfunction "PC11_52") (pintype "bidirectional"))
    )
    (net (code "84") (name "unconnected-(STM32F-PC14-Pad3)") (class "Default")
      (node (ref "STM32") (pin "3") (pinfunction "PC14_3") (pintype "bidirectional"))
    )
    (net (code "85") (name "unconnected-(STM32G-PC0-Pad8)") (class "Default")
      (node (ref "STM32") (pin "8") (pinfunction "PC0_8") (pintype "bidirectional"))
    )
    (net (code "86") (name "unconnected-(STM32G-PC4-Pad24)") (class "Default")
      (node (ref "STM32") (pin "24") (pinfunction "PC4_24") (pintype "bidirectional"))
    )
    (net (code "87") (name "unconnected-(STM32G-PC5-Pad25)") (class "Default")
      (node (ref "STM32") (pin "25") (pinfunction "PC5_25") (pintype "bidirectional"))
    )
    (net (code "88") (name "unconnected-(STM32H-PD2-Pad54)") (class "Default")
      (node (ref "STM32") (pin "54") (pinfunction "PD2_54") (pintype "bidirectional"))
    )
    (net (code "89") (name "unconnected-(TVS2-IO-Pad1)") (class "Default")
      (node (ref "TVS2") (pin "1") (pinfunction "IO_1") (pintype "bidirectional"))
    )
    (net (code "90") (name "unconnected-(TVS2-IO-Pad6)") (class "Default")
      (node (ref "TVS2") (pin "6") (pinfunction "IO_6") (pintype "bidirectional"))
    )
  )
)
